# SW_ANT.net
KiCad netlist of a schematic drawn in Altium Designer
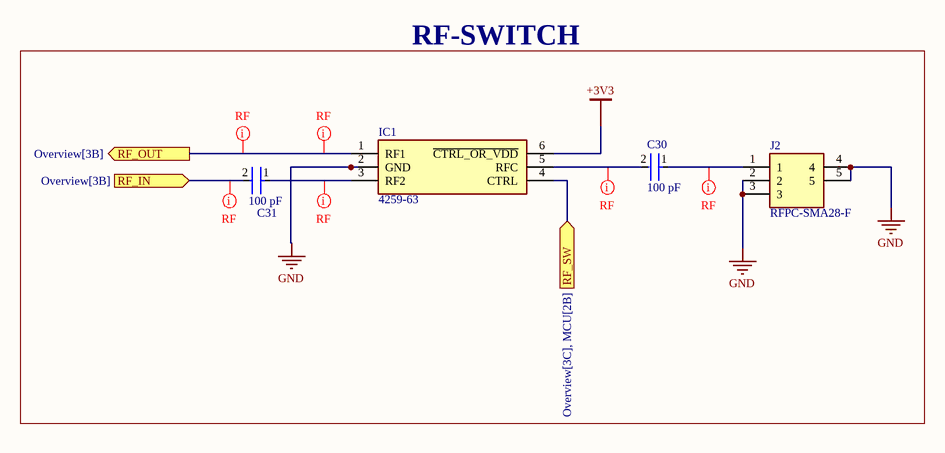
[diagram p0: SW_ANT.SchDoc]

(export (version "E")
  (design (tool "Eeschema 10.0.6"))
  (components
    (comp (ref "C30")
      (value "100 pF")
      (footprint "FP-GQM187-0_15-MFG")
      (description "Ceramic Capacitor 100pF ±5% 250VDC C0G 0603 Paper T/R Name: GQM1875C2E101JB12D")
      (fields (field (name "TOLERANCE") "5%"))
      (libsource (lib "Altium Content Vault") (part "02cd4be3c70576c341d710602a673aa"))
    )
    (comp (ref "C31")
      (value "100 pF")
      (footprint "FP-GQM187-0_15-MFG")
      (description "Ceramic Capacitor 100pF ±5% 250VDC C0G 0603 Paper T/R Name: GQM1875C2E101JB12D")
      (fields (field (name "TOLERANCE") "5%"))
      (libsource (lib "Altium Content Vault") (part "02cd4be3c70576c341d710602a673aa"))
    )
    (comp (ref "IC1")
      (value "4259-63")
      (footprint "SamacSys:SOT65P210X110-6N")
      (description "Integrated Circuit")
      (fields (field (name "MOUSER PART NUMBER") "81-4259-63"))
      (libsource (lib "*") (part "4259-63"))
    )
    (comp (ref "J2")
      (value "RFPC-SMA28-F")
      (footprint "SamacSys:RFPCSMA28F")
      (description "Connector")
      (libsource (lib "*") (part "RFPC-SMA28-F"))
    )
  )
  (nets
    (net (code "1") (name "+3V3") (class "Default")
      (node (ref "IC1") (pin "6") (pinfunction "~{CTRL_OR_VDD}_6") (pintype "passive"))
    )
    (net (code "2") (name "/RF_IN") (class "Default")
      (node (ref "C31") (pin "2") (pinfunction "2_2") (pintype "passive"))
    )
    (net (code "3") (name "/RF_OUT") (class "Default")
      (node (ref "IC1") (pin "1") (pinfunction "RF1_1") (pintype "passive"))
    )
    (net (code "4") (name "/RF_SW") (class "Default")
      (node (ref "IC1") (pin "4") (pinfunction "CTRL_4") (pintype "passive"))
    )
    (net (code "5") (name "GND") (class "Default")
      (node (ref "IC1") (pin "2") (pinfunction "GND_2") (pintype "passive"))
      (node (ref "J2") (pin "2") (pinfunction "2_2") (pintype "passive"))
      (node (ref "J2") (pin "3") (pinfunction "3_3") (pintype "passive"))
      (node (ref "J2") (pin "4") (pinfunction "4_4") (pintype "passive"))
      (node (ref "J2") (pin "5") (pinfunction "5_5") (pintype "passive"))
    )
    (net (code "6") (name "Net-(C30-Pad1)") (class "Default")
      (node (ref "C30") (pin "1") (pinfunction "1_1") (pintype "passive"))
      (node (ref "J2") (pin "1") (pinfunction "1_1") (pintype "passive"))
    )
    (net (code "7") (name "Net-(IC1-RF2)") (class "Default")
      (node (ref "C31") (pin "1") (pinfunction "1_1") (pintype "passive"))
      (node (ref "IC1") (pin "3") (pinfunction "RF2_3") (pintype "passive"))
    )
    (net (code "8") (name "Net-(IC1-RFC)") (class "Default")
      (node (ref "C30") (pin "2") (pinfunction "2_2") (pintype "passive"))
      (node (ref "IC1") (pin "5") (pinfunction "RFC_5") (pintype "passive"))
    )
  )
)
